# phase_v3.net
KiCad netlist of a schematic drawn in EAGLE
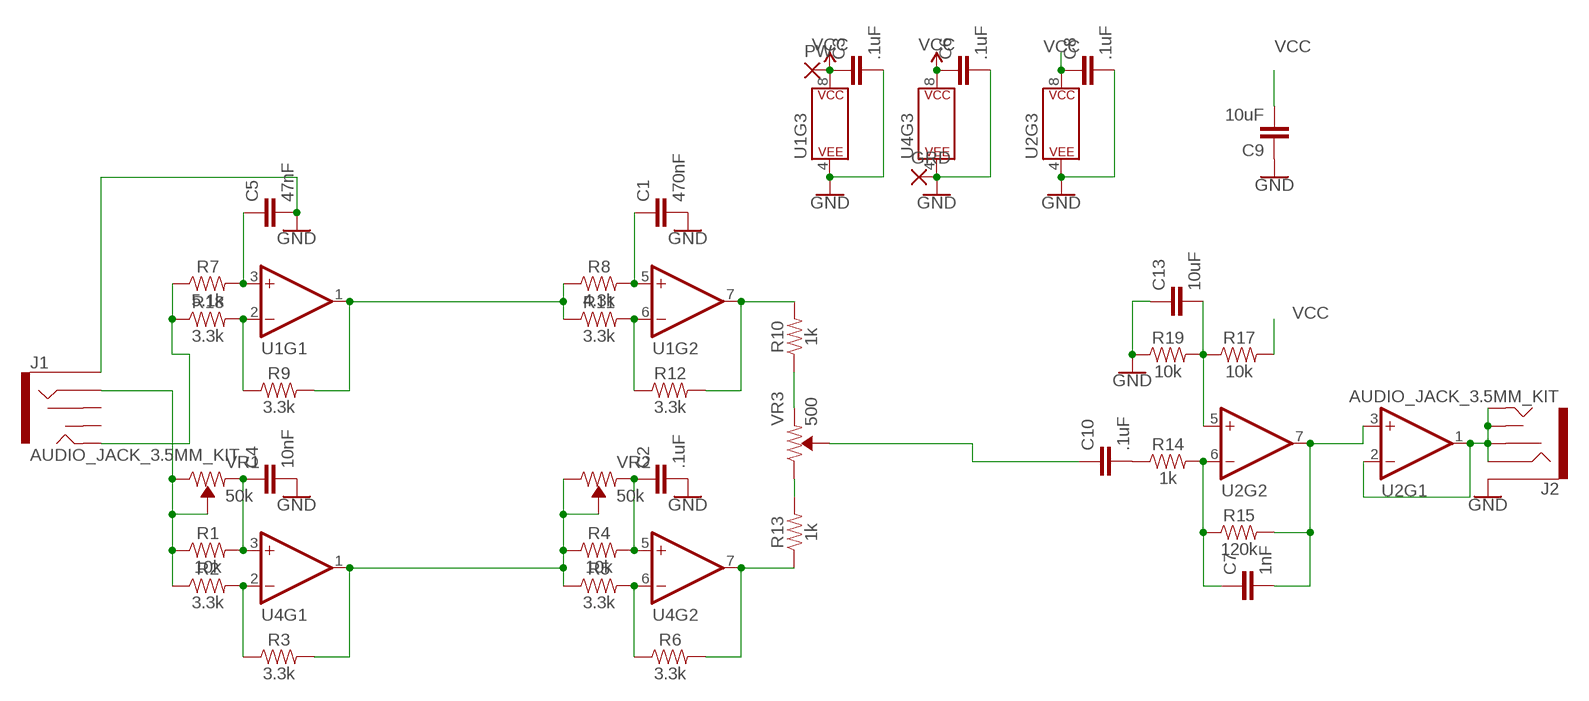
[diagram p0: schematic, sheet 1]

(export (version "E")
  (design (tool "Eeschema 10.0.6"))
  (components
    (comp (ref "C1")
      (value "470nF")
      (footprint "eagle-import:0805")
      (libsource (lib "eagle-import") (part "1.0UF-0805-25V-(+80/-20%)"))
    )
    (comp (ref "C2")
      (value ".1uF")
      (footprint "eagle-import:0805")
      (libsource (lib "eagle-import") (part "1.0UF-0805-25V-(+80/-20%)"))
    )
    (comp (ref "C3")
      (value ".1uF")
      (footprint "eagle-import:0805")
      (libsource (lib "eagle-import") (part "1.0UF-0805-25V-(+80/-20%)"))
    )
    (comp (ref "C4")
      (value "10nF")
      (footprint "eagle-import:0805")
      (libsource (lib "eagle-import") (part "1.0UF-0805-25V-(+80/-20%)"))
    )
    (comp (ref "C5")
      (value "47nF")
      (footprint "eagle-import:0805")
      (libsource (lib "eagle-import") (part "1.0UF-0805-25V-(+80/-20%)"))
    )
    (comp (ref "C6")
      (value ".1uF")
      (footprint "eagle-import:0805")
      (libsource (lib "eagle-import") (part "1.0UF-0805-25V-(+80/-20%)"))
    )
    (comp (ref "C7")
      (value "1nF")
      (footprint "eagle-import:0805")
      (libsource (lib "eagle-import") (part "1.0UF-0805-25V-(+80/-20%)"))
    )
    (comp (ref "C8")
      (value ".1uF")
      (footprint "eagle-import:0805")
      (libsource (lib "eagle-import") (part "1.0UF-0805-25V-(+80/-20%)"))
    )
    (comp (ref "C9")
      (value "10uF")
      (footprint "eagle-import:C5B3.5")
      (libsource (lib "eagle-import") (part "C5/3.5"))
    )
    (comp (ref "C10")
      (value ".1uF")
      (footprint "eagle-import:0805")
      (libsource (lib "eagle-import") (part "1.0UF-0805-25V-(+80/-20%)"))
    )
    (comp (ref "C13")
      (value "10uF")
      (footprint "eagle-import:C5B3.5")
      (libsource (lib "eagle-import") (part "C5/3.5"))
    )
    (comp (ref "GRD")
      (value "2,54/1,1")
      (footprint "eagle-import:2,54_1,1")
      (libsource (lib "eagle-import") (part "2,54/1,1"))
    )
    (comp (ref "J1")
      (value "AUDIO_JACK_3.5MM_KIT")
      (footprint "eagle-import:AUDIO-JACK-KIT")
      (libsource (lib "eagle-import") (part "AUDIO_JACK_3.5MM_KIT"))
    )
    (comp (ref "J2")
      (value "AUDIO_JACK_3.5MM_KIT")
      (footprint "eagle-import:AUDIO-JACK-KIT")
      (libsource (lib "eagle-import") (part "AUDIO_JACK_3.5MM_KIT"))
    )
    (comp (ref "PW")
      (value "2,54/1,1")
      (footprint "eagle-import:2,54_1,1")
      (libsource (lib "eagle-import") (part "2,54/1,1"))
    )
    (comp (ref "R1")
      (value "10k")
      (footprint "eagle-import:0805")
      (libsource (lib "eagle-import") (part "0.3OHM-0805-1/8W-1%"))
    )
    (comp (ref "R2")
      (value "3.3k")
      (footprint "eagle-import:0805")
      (libsource (lib "eagle-import") (part "0.3OHM-0805-1/8W-1%"))
    )
    (comp (ref "R3")
      (value "3.3k")
      (footprint "eagle-import:0805")
      (libsource (lib "eagle-import") (part "0.3OHM-0805-1/8W-1%"))
    )
    (comp (ref "R4")
      (value "10k")
      (footprint "eagle-import:0805")
      (libsource (lib "eagle-import") (part "0.3OHM-0805-1/8W-1%"))
    )
    (comp (ref "R5")
      (value "3.3k")
      (footprint "eagle-import:0805")
      (libsource (lib "eagle-import") (part "0.3OHM-0805-1/8W-1%"))
    )
    (comp (ref "R6")
      (value "3.3k")
      (footprint "eagle-import:0805")
      (libsource (lib "eagle-import") (part "0.3OHM-0805-1/8W-1%"))
    )
    (comp (ref "R7")
      (value "5.1k")
      (footprint "eagle-import:0805")
      (libsource (lib "eagle-import") (part "0.3OHM-0805-1/8W-1%"))
    )
    (comp (ref "R8")
      (value "4.3k")
      (footprint "eagle-import:0805")
      (libsource (lib "eagle-import") (part "0.3OHM-0805-1/8W-1%"))
    )
    (comp (ref "R9")
      (value "3.3k")
      (footprint "eagle-import:0805")
      (libsource (lib "eagle-import") (part "0.3OHM-0805-1/8W-1%"))
    )
    (comp (ref "R10")
      (value "1k")
      (footprint "eagle-import:0805")
      (libsource (lib "eagle-import") (part "0.3OHM-0805-1/8W-1%"))
    )
    (comp (ref "R11")
      (value "3.3k")
      (footprint "eagle-import:0805")
      (libsource (lib "eagle-import") (part "0.3OHM-0805-1/8W-1%"))
    )
    (comp (ref "R12")
      (value "3.3k")
      (footprint "eagle-import:0805")
      (libsource (lib "eagle-import") (part "0.3OHM-0805-1/8W-1%"))
    )
    (comp (ref "R13")
      (value "1k")
      (footprint "eagle-import:0805")
      (libsource (lib "eagle-import") (part "0.3OHM-0805-1/8W-1%"))
    )
    (comp (ref "R14")
      (value "1k")
      (footprint "eagle-import:0805")
      (libsource (lib "eagle-import") (part "0.3OHM-0805-1/8W-1%"))
    )
    (comp (ref "R15")
      (value "120k")
      (footprint "eagle-import:0805")
      (libsource (lib "eagle-import") (part "0.3OHM-0805-1/8W-1%"))
    )
    (comp (ref "R17")
      (value "10k")
      (footprint "eagle-import:0805")
      (libsource (lib "eagle-import") (part "0.3OHM-0805-1/8W-1%"))
    )
    (comp (ref "R18")
      (value "3.3k")
      (footprint "eagle-import:0805")
      (libsource (lib "eagle-import") (part "0.3OHM-0805-1/8W-1%"))
    )
    (comp (ref "R19")
      (value "10k")
      (footprint "eagle-import:0805")
      (libsource (lib "eagle-import") (part "0.3OHM-0805-1/8W-1%"))
    )
    (comp (ref "U1")
      (value "LM358DIP08-SOIC")
      (footprint "eagle-import:SO08")
      (libsource (lib "eagle-import") (part "LM358DIP08-SOIC"))
    )
    (comp (ref "U2")
      (value "LM358DIP08-SOIC")
      (footprint "eagle-import:SO08")
      (libsource (lib "eagle-import") (part "LM358DIP08-SOIC"))
    )
    (comp (ref "U4")
      (value "LM358DIP08-SOIC")
      (footprint "eagle-import:SO08")
      (libsource (lib "eagle-import") (part "LM358DIP08-SOIC"))
    )
    (comp (ref "VR1")
      (value "50k")
      (footprint "eagle-import:TRIMPOT-PTH-3386U")
      (libsource (lib "eagle-import") (part "TRIMPOT-PTH-10MM-KNOB-1/2W-10%"))
    )
    (comp (ref "VR2")
      (value "50k")
      (footprint "eagle-import:TRIMPOT-PTH-3386U")
      (libsource (lib "eagle-import") (part "TRIMPOT-PTH-10MM-KNOB-1/2W-10%"))
    )
    (comp (ref "VR3")
      (value "500")
      (footprint "eagle-import:TRIMPOT-PTH-3386U")
      (libsource (lib "eagle-import") (part "TRIMPOT-PTH-10MM-KNOB-1/2W-10%"))
    )
  )
  (nets
    (net (code "1") (name "GND") (class "Default")
      (node (ref "C1") (pin "2") (pinfunction "2_2") (pintype "passive"))
      (node (ref "C13") (pin "1") (pinfunction "1_1") (pintype "passive"))
      (node (ref "C2") (pin "2") (pinfunction "2_2") (pintype "passive"))
      (node (ref "C3") (pin "2") (pinfunction "2_2") (pintype "passive"))
      (node (ref "C4") (pin "2") (pinfunction "2_2") (pintype "passive"))
      (node (ref "C5") (pin "2") (pinfunction "2_2") (pintype "passive"))
      (node (ref "C6") (pin "2") (pinfunction "2_2") (pintype "passive"))
      (node (ref "C8") (pin "2") (pinfunction "2_2") (pintype "passive"))
      (node (ref "C9") (pin "1") (pinfunction "1_1") (pintype "passive"))
      (node (ref "GRD") (pin "1") (pinfunction "P_1") (pintype "passive"))
      (node (ref "J1") (pin "SLEEVE") (pinfunction "SLEEVE_SLEEVE") (pintype "bidirectional"))
      (node (ref "J2") (pin "SLEEVE") (pinfunction "SLEEVE_SLEEVE") (pintype "bidirectional"))
      (node (ref "R19") (pin "1") (pinfunction "1_1") (pintype "passive"))
      (node (ref "U1") (pin "4") (pinfunction "P$V-_4") (pintype "bidirectional"))
      (node (ref "U2") (pin "4") (pinfunction "P$V-_4") (pintype "bidirectional"))
      (node (ref "U4") (pin "4") (pinfunction "P$V-_4") (pintype "bidirectional"))
    )
    (net (code "2") (name "Net-(C10-Pad2)") (class "Default")
      (node (ref "C10") (pin "2") (pinfunction "2_2") (pintype "passive"))
      (node (ref "R14") (pin "1") (pinfunction "1_1") (pintype "passive"))
    )
    (net (code "3") (name "Net-(J1-PadTIP)") (class "Default")
      (node (ref "J1") (pin "TIP") (pinfunction "TIP_TIP") (pintype "bidirectional"))
      (node (ref "R18") (pin "1") (pinfunction "1_1") (pintype "passive"))
      (node (ref "R7") (pin "1") (pinfunction "1_1") (pintype "passive"))
    )
    (net (code "4") (name "Net-(U1A-+IN)") (class "Default")
      (node (ref "C5") (pin "1") (pinfunction "1_1") (pintype "passive"))
      (node (ref "R7") (pin "2") (pinfunction "2_2") (pintype "passive"))
      (node (ref "U1") (pin "3") (pinfunction "+IN_3") (pintype "input"))
    )
    (net (code "5") (name "Net-(U1A--IN)") (class "Default")
      (node (ref "R18") (pin "2") (pinfunction "2_2") (pintype "passive"))
      (node (ref "R9") (pin "1") (pinfunction "1_1") (pintype "passive"))
      (node (ref "U1") (pin "2") (pinfunction "-IN_2") (pintype "input"))
    )
    (net (code "6") (name "Net-(U1A-OUT)") (class "Default")
      (node (ref "R11") (pin "1") (pinfunction "1_1") (pintype "passive"))
      (node (ref "R8") (pin "1") (pinfunction "1_1") (pintype "passive"))
      (node (ref "R9") (pin "2") (pinfunction "2_2") (pintype "passive"))
      (node (ref "U1") (pin "1") (pinfunction "OUT_1") (pintype "output"))
    )
    (net (code "7") (name "Net-(U1B-+IN)") (class "Default")
      (node (ref "C1") (pin "1") (pinfunction "1_1") (pintype "passive"))
      (node (ref "R8") (pin "2") (pinfunction "2_2") (pintype "passive"))
      (node (ref "U1") (pin "5") (pinfunction "+IN_5") (pintype "input"))
    )
    (net (code "8") (name "Net-(U1B--IN)") (class "Default")
      (node (ref "R11") (pin "2") (pinfunction "2_2") (pintype "passive"))
      (node (ref "R12") (pin "1") (pinfunction "1_1") (pintype "passive"))
      (node (ref "U1") (pin "6") (pinfunction "-IN_6") (pintype "input"))
    )
    (net (code "9") (name "Net-(U1B-OUT)") (class "Default")
      (node (ref "R10") (pin "2") (pinfunction "2_2") (pintype "passive"))
      (node (ref "R12") (pin "2") (pinfunction "2_2") (pintype "passive"))
      (node (ref "U1") (pin "7") (pinfunction "OUT_7") (pintype "output"))
    )
    (net (code "10") (name "Net-(U2A-+IN)") (class "Default")
      (node (ref "C7") (pin "2") (pinfunction "2_2") (pintype "passive"))
      (node (ref "R15") (pin "2") (pinfunction "2_2") (pintype "passive"))
      (node (ref "U2") (pin "3") (pinfunction "+IN_3") (pintype "input"))
      (node (ref "U2") (pin "7") (pinfunction "OUT_7") (pintype "output"))
    )
    (net (code "11") (name "Net-(U2A--IN)") (class "Default")
      (node (ref "J2") (pin "RING") (pinfunction "RING_RING") (pintype "bidirectional"))
      (node (ref "J2") (pin "RSH") (pinfunction "RSH_RSH") (pintype "bidirectional"))
      (node (ref "J2") (pin "TIP") (pinfunction "TIP_TIP") (pintype "bidirectional"))
      (node (ref "J2") (pin "TSH") (pinfunction "TSH_TSH") (pintype "bidirectional"))
      (node (ref "U2") (pin "1") (pinfunction "OUT_1") (pintype "output"))
      (node (ref "U2") (pin "2") (pinfunction "-IN_2") (pintype "input"))
    )
    (net (code "12") (name "Net-(U2B-+IN)") (class "Default")
      (node (ref "C13") (pin "2") (pinfunction "2_2") (pintype "passive"))
      (node (ref "R17") (pin "1") (pinfunction "1_1") (pintype "passive"))
      (node (ref "R19") (pin "2") (pinfunction "2_2") (pintype "passive"))
      (node (ref "U2") (pin "5") (pinfunction "+IN_5") (pintype "input"))
    )
    (net (code "13") (name "Net-(U2B--IN)") (class "Default")
      (node (ref "C7") (pin "1") (pinfunction "1_1") (pintype "passive"))
      (node (ref "R14") (pin "2") (pinfunction "2_2") (pintype "passive"))
      (node (ref "R15") (pin "1") (pinfunction "1_1") (pintype "passive"))
      (node (ref "U2") (pin "6") (pinfunction "-IN_6") (pintype "input"))
    )
    (net (code "14") (name "Net-(U4A-+IN)") (class "Default")
      (node (ref "C4") (pin "1") (pinfunction "1_1") (pintype "passive"))
      (node (ref "R1") (pin "2") (pinfunction "2_2") (pintype "passive"))
      (node (ref "U4") (pin "3") (pinfunction "+IN_3") (pintype "input"))
      (node (ref "VR1") (pin "1") (pinfunction "CCW_1") (pintype "passive"))
    )
    (net (code "15") (name "Net-(U4A--IN)") (class "Default")
      (node (ref "R2") (pin "2") (pinfunction "2_2") (pintype "passive"))
      (node (ref "R3") (pin "1") (pinfunction "1_1") (pintype "passive"))
      (node (ref "U4") (pin "2") (pinfunction "-IN_2") (pintype "input"))
    )
    (net (code "16") (name "Net-(U4A-OUT)") (class "Default")
      (node (ref "R3") (pin "2") (pinfunction "2_2") (pintype "passive"))
      (node (ref "R4") (pin "1") (pinfunction "1_1") (pintype "passive"))
      (node (ref "R5") (pin "1") (pinfunction "1_1") (pintype "passive"))
      (node (ref "U4") (pin "1") (pinfunction "OUT_1") (pintype "output"))
      (node (ref "VR2") (pin "2") (pinfunction "WIPER_2") (pintype "passive"))
      (node (ref "VR2") (pin "3") (pinfunction "CW_3") (pintype "passive"))
    )
    (net (code "17") (name "Net-(U4B-+IN)") (class "Default")
      (node (ref "C2") (pin "1") (pinfunction "1_1") (pintype "passive"))
      (node (ref "R4") (pin "2") (pinfunction "2_2") (pintype "passive"))
      (node (ref "U4") (pin "5") (pinfunction "+IN_5") (pintype "input"))
      (node (ref "VR2") (pin "1") (pinfunction "CCW_1") (pintype "passive"))
    )
    (net (code "18") (name "Net-(U4B--IN)") (class "Default")
      (node (ref "R5") (pin "2") (pinfunction "2_2") (pintype "passive"))
      (node (ref "R6") (pin "1") (pinfunction "1_1") (pintype "passive"))
      (node (ref "U4") (pin "6") (pinfunction "-IN_6") (pintype "input"))
    )
    (net (code "19") (name "Net-(U4B-OUT)") (class "Default")
      (node (ref "R13") (pin "1") (pinfunction "1_1") (pintype "passive"))
      (node (ref "R6") (pin "2") (pinfunction "2_2") (pintype "passive"))
      (node (ref "U4") (pin "7") (pinfunction "OUT_7") (pintype "output"))
    )
    (net (code "20") (name "Net-(VR1-CW)") (class "Default")
      (node (ref "J1") (pin "RING") (pinfunction "RING_RING") (pintype "bidirectional"))
      (node (ref "R1") (pin "1") (pinfunction "1_1") (pintype "passive"))
      (node (ref "R2") (pin "1") (pinfunction "1_1") (pintype "passive"))
      (node (ref "VR1") (pin "2") (pinfunction "WIPER_2") (pintype "passive"))
      (node (ref "VR1") (pin "3") (pinfunction "CW_3") (pintype "passive"))
    )
    (net (code "21") (name "Net-(VR3-CCW)") (class "Default")
      (node (ref "R10") (pin "1") (pinfunction "1_1") (pintype "passive"))
      (node (ref "VR3") (pin "1") (pinfunction "CCW_1") (pintype "passive"))
    )
    (net (code "22") (name "Net-(VR3-CW)") (class "Default")
      (node (ref "R13") (pin "2") (pinfunction "2_2") (pintype "passive"))
      (node (ref "VR3") (pin "3") (pinfunction "CW_3") (pintype "passive"))
    )
    (net (code "23") (name "Net-(VR3-WIPER)") (class "Default")
      (node (ref "C10") (pin "1") (pinfunction "1_1") (pintype "passive"))
      (node (ref "VR3") (pin "2") (pinfunction "WIPER_2") (pintype "passive"))
    )
    (net (code "24") (name "VCC") (class "Default")
      (node (ref "C3") (pin "1") (pinfunction "1_1") (pintype "passive"))
      (node (ref "C6") (pin "1") (pinfunction "1_1") (pintype "passive"))
      (node (ref "C8") (pin "1") (pinfunction "1_1") (pintype "passive"))
      (node (ref "C9") (pin "2") (pinfunction "2_2") (pintype "passive"))
      (node (ref "PW") (pin "1") (pinfunction "P_1") (pintype "passive"))
      (node (ref "R17") (pin "2") (pinfunction "2_2") (pintype "passive"))
      (node (ref "U1") (pin "8") (pinfunction "P$V+_8") (pintype "bidirectional"))
      (node (ref "U2") (pin "8") (pinfunction "P$V+_8") (pintype "bidirectional"))
      (node (ref "U4") (pin "8") (pinfunction "P$V+_8") (pintype "bidirectional"))
    )
    (net (code "25") (name "unconnected-(J1-PadRSH)") (class "Default")
      (node (ref "J1") (pin "RSH") (pinfunction "RSH_RSH") (pintype "bidirectional"))
    )
    (net (code "26") (name "unconnected-(J1-PadTSH)") (class "Default")
      (node (ref "J1") (pin "TSH") (pinfunction "TSH_TSH") (pintype "bidirectional"))
    )
  )
)
